# Antena.net
KiCad netlist of a schematic drawn in Altium Designer
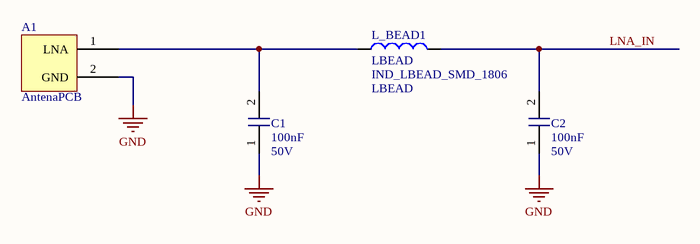
[diagram p0: Antena.SchDoc]

(export (version "E")
  (design (tool "Eeschema 10.0.6"))
  (components
    (comp (ref "A1")
      (value "AntenaPCB")
      (footprint "PCBComponent_1")
      (libsource (lib "AntenaPCB") (part "AntenaPCB"))
    )
    (comp (ref "C1")
      (value "CAP 100nF/50V")
      (footprint "CAP 100nF/50V")
      (description "0.1µF ±10% 50V Ceramic Capacitor X5R 0402 (1005 Metric)")
      (fields (field (name "CAPACITANCE") "100nF") (field (name "VOLTAGE") "50V"))
      (libsource (lib "Ceramic Capacitors 0402 50V") (part "CAP 100nF/50V"))
    )
    (comp (ref "C2")
      (value "CAP 100nF/50V")
      (footprint "CAP 100nF/50V")
      (description "0.1µF ±10% 50V Ceramic Capacitor X5R 0402 (1005 Metric)")
      (fields (field (name "CAPACITANCE") "100nF") (field (name "VOLTAGE") "50V"))
      (libsource (lib "Ceramic Capacitors 0402 50V") (part "CAP 100nF/50V"))
    )
    (comp (ref "L_BEAD1")
      (value "LBEAD")
      (footprint "IND_LBEAD_SMD_1806")
      (description "Inductor LBEAD")
      (fields (field (name "ALTIUM_VALUE") "LBEAD"))
      (libsource (lib "i9Library_Altium") (part "IND_LBEAD_SMD_1806"))
    )
  )
  (nets
    (net (code "1") (name "/LNA_IN") (class "Default")
      (node (ref "C2") (pin "2") (pinfunction "2_2") (pintype "passive"))
      (node (ref "L_BEAD1") (pin "2") (pintype "passive"))
    )
    (net (code "2") (name "GND") (class "Default")
      (node (ref "A1") (pin "2") (pinfunction "GND_2") (pintype "passive"))
      (node (ref "C1") (pin "1") (pinfunction "1_1") (pintype "passive"))
      (node (ref "C2") (pin "1") (pinfunction "1_1") (pintype "passive"))
    )
    (net (code "3") (name "Net-(A1-LNA)") (class "Default")
      (node (ref "A1") (pin "1") (pinfunction "LNA_1") (pintype "passive"))
      (node (ref "C1") (pin "2") (pinfunction "2_2") (pintype "passive"))
      (node (ref "L_BEAD1") (pin "1") (pintype "passive"))
    )
  )
)
